# 1-Schematic_RFID_WAVER.net
KiCad netlist of a schematic drawn in EasyEDA
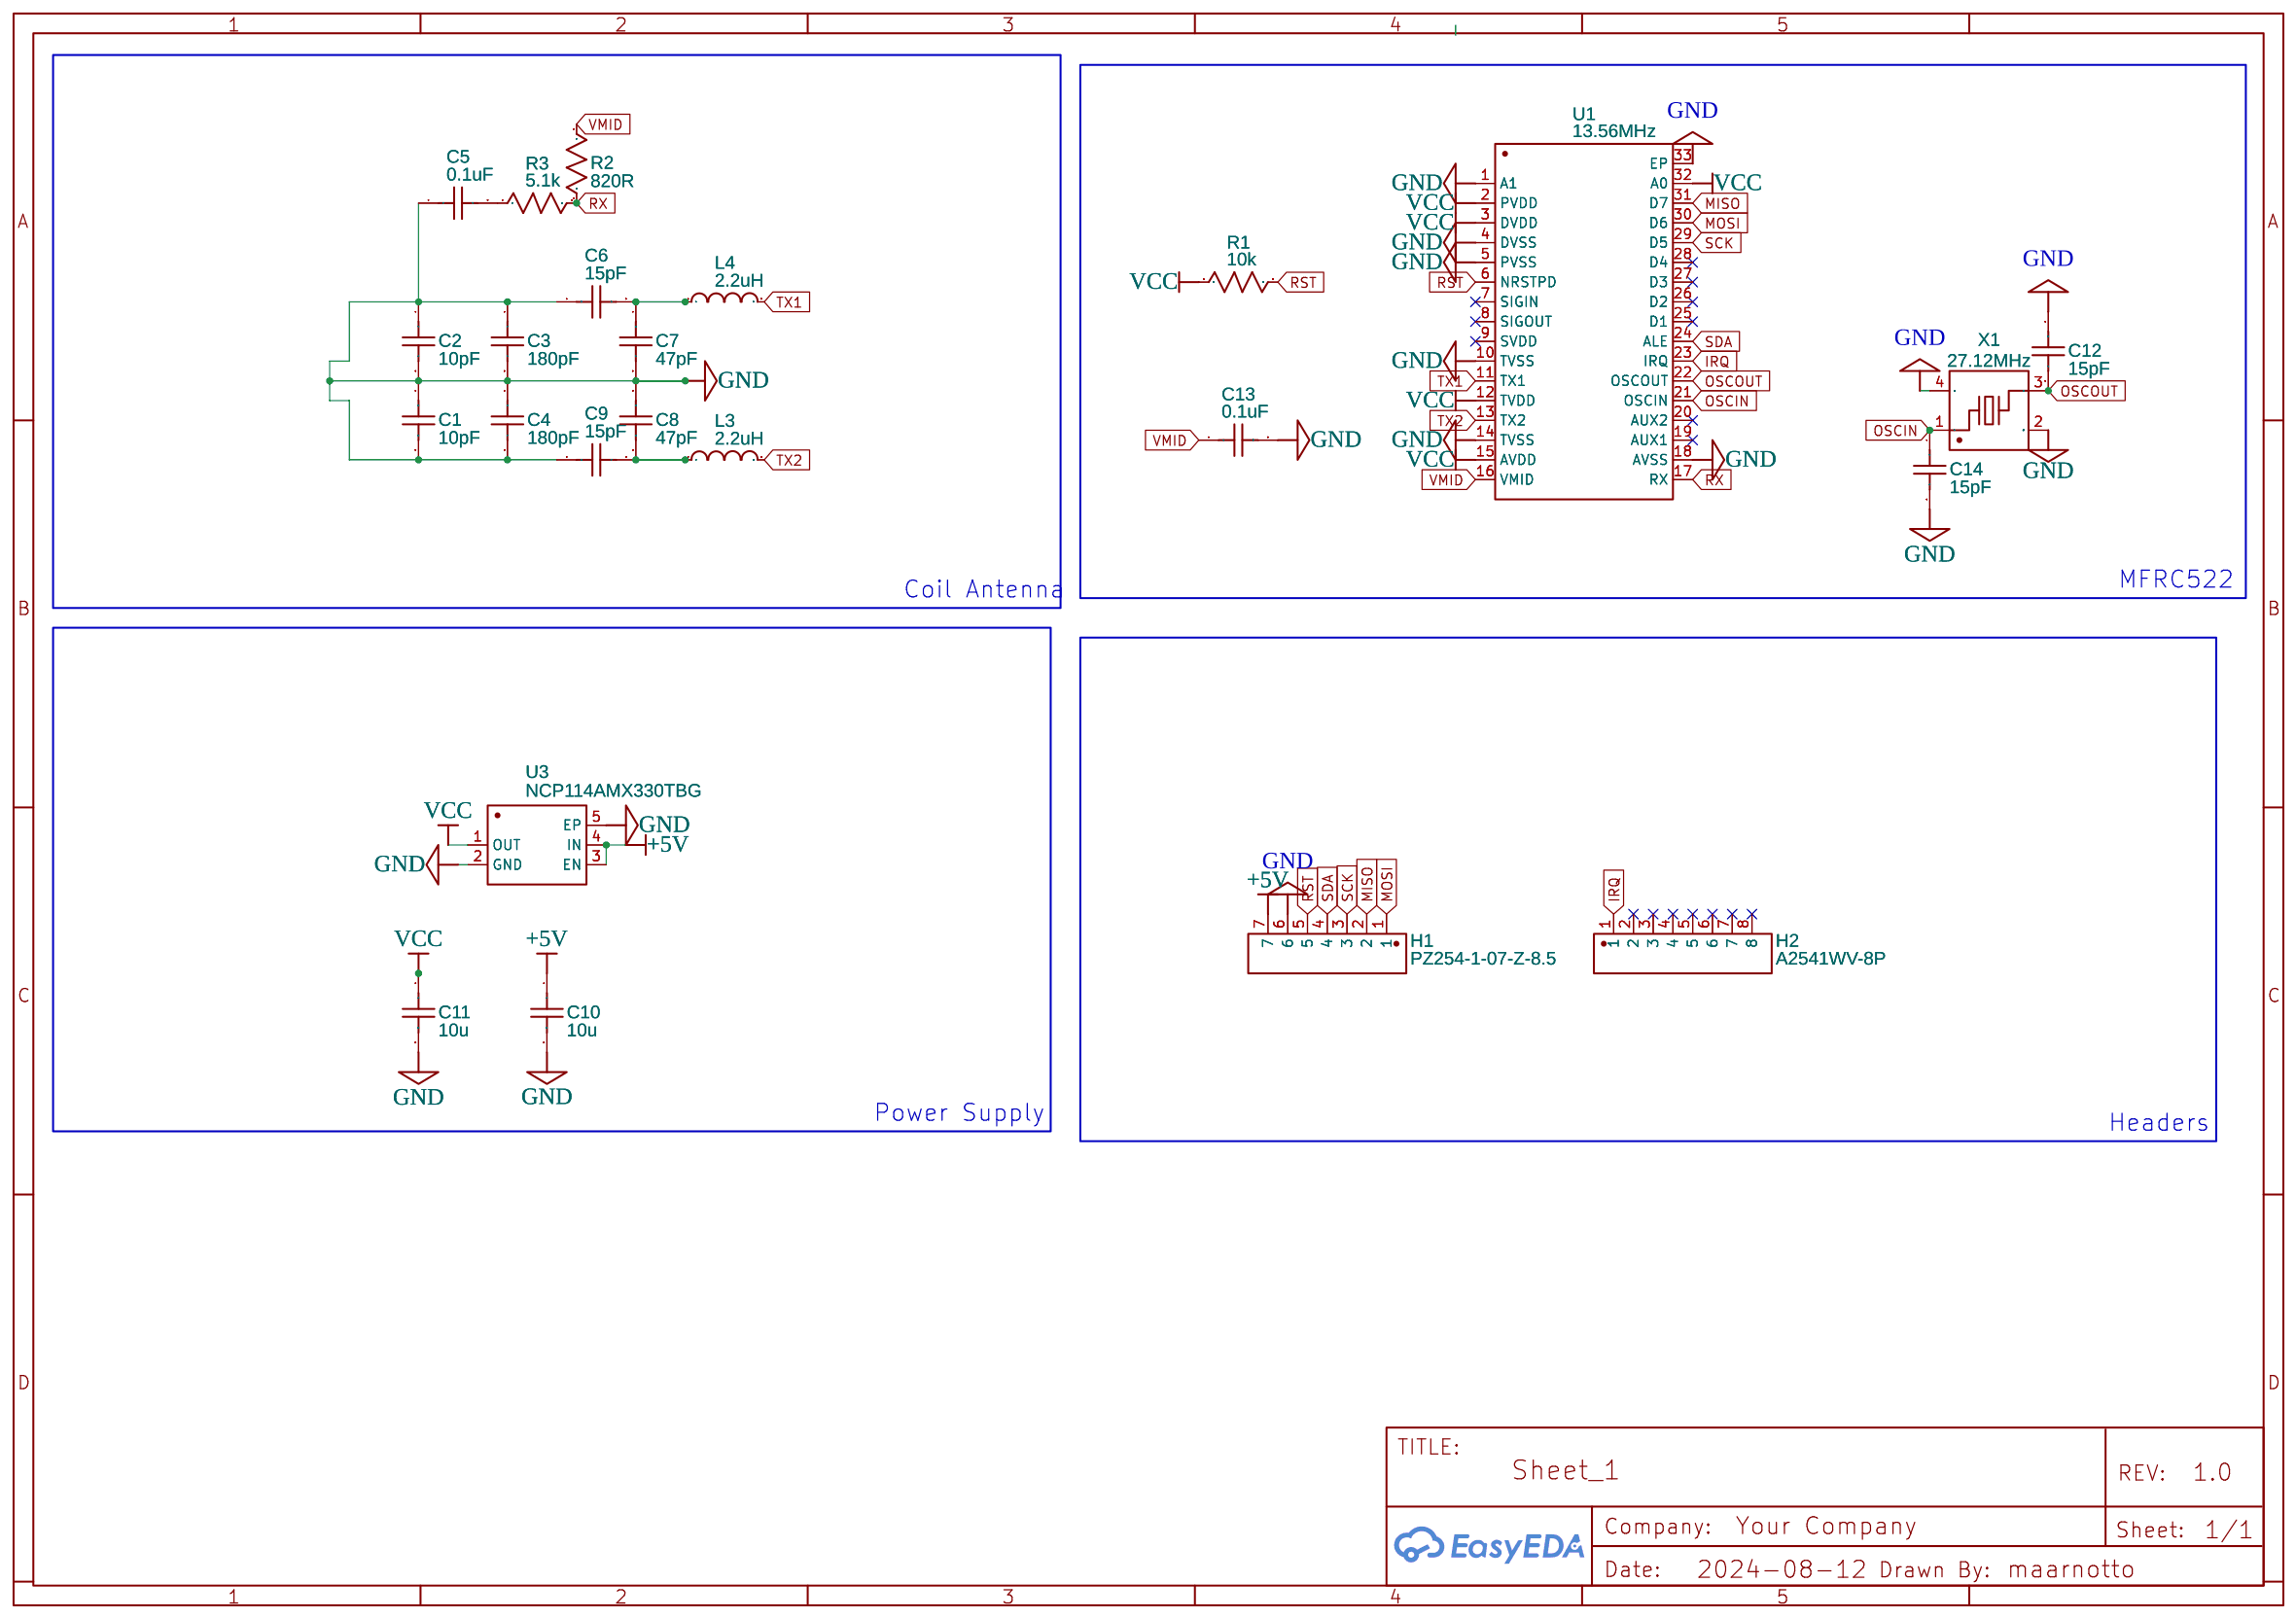
[diagram p0: schematic sheet]

(export (version "E")
  (design (tool "Eeschema 10.0.6"))
  (components
    (comp (ref "C1") (value "10pF") (libsource (lib "") (part "C_0603_US")))
    (comp (ref "C2") (value "10pF") (libsource (lib "") (part "C_0603_US")))
    (comp (ref "C3") (value "180pF") (libsource (lib "") (part "C_0603_US")))
    (comp (ref "C4") (value "180pF") (libsource (lib "") (part "C_0603_US")))
    (comp (ref "C5") (value "0.1uF") (libsource (lib "") (part "C_0603_US_1")))
    (comp (ref "C6") (value "15pF") (libsource (lib "") (part "C_0603_US_1")))
    (comp (ref "C7") (value "47pF") (libsource (lib "") (part "C_0603_US")))
    (comp (ref "C8") (value "47pF") (libsource (lib "") (part "C_0603_US")))
    (comp (ref "C9") (value "15pF") (libsource (lib "") (part "C_0603_US_1")))
    (comp (ref "C10") (value "10u") (libsource (lib "") (part "C_0603_US")))
    (comp (ref "C11") (value "10u") (libsource (lib "") (part "C_0603_US")))
    (comp (ref "C12") (value "15pF") (libsource (lib "") (part "C_0603_US")))
    (comp (ref "C13") (value "0.1uF") (libsource (lib "") (part "C_0603_US_1")))
    (comp (ref "C14") (value "15pF") (libsource (lib "") (part "C_0603_US")))
    (comp (ref "H1")
      (value "PZ254-1-07-Z-8.5")
      (fields (field (name "Manufacturer") "HCTL(华灿天禄)"))
      (libsource (lib "") (part "PZ254-1-07-Z-8.5"))
    )
    (comp (ref "H2")
      (value "A2541WV-8P")
      (fields (field (name "Manufacturer") "CJT(长江连接器)"))
      (libsource (lib "") (part "A2541WV-8P"))
    )
    (comp (ref "L3") (value "2.2uH") (libsource (lib "") (part "L0603_US")))
    (comp (ref "L4") (value "2.2uH") (libsource (lib "") (part "L0603_US")))
    (comp (ref "R1") (value "10k") (libsource (lib "") (part "R_0603_US")))
    (comp (ref "R2") (value "820R") (libsource (lib "") (part "R_0603_US_1")))
    (comp (ref "R3") (value "5.1k") (libsource (lib "") (part "R_0603_US")))
    (comp (ref "U1")
      (value "13.56MHz")
      (fields (field (name "Manufacturer Part") "MFRC522") (field (name "Manufacturer") "JSMSEMI(杰盛微)"))
      (libsource (lib "") (part "MFRC522"))
    )
    (comp (ref "U3")
      (value "NCP114AMX330TBG")
      (fields (field (name "Manufacturer") "onsemi(安森美)"))
      (libsource (lib "") (part "NCP114AMX330TBG"))
    )
    (comp (ref "X1")
      (value "27.12MHz")
      (fields
        (field (name "Manufacturer Part") "XL2EL89CMI-111YLC-27.12M")
        (field (name "Manufacturer") "YXC(扬兴晶振)")
      )
      (libsource (lib "") (part "XL2EL89CMI-111YLC-27.12M"))
    )
  )
  (nets
    (net (code "1") (name "+5V") (class "Default")
      (node (ref "C10") (pin "1") (pinfunction "1_1") (pintype "unspecified"))
      (node (ref "H1") (pin "7") (pinfunction "7_7") (pintype "unspecified"))
      (node (ref "U3") (pin "3") (pinfunction "EN_3") (pintype "unspecified"))
      (node (ref "U3") (pin "4") (pinfunction "IN_4") (pintype "unspecified"))
    )
    (net (code "2") (name "GND") (class "Default")
      (node (ref "C1") (pin "1") (pinfunction "1_1") (pintype "unspecified"))
      (node (ref "C1") (pin "2") (pinfunction "2_2") (pintype "unspecified"))
      (node (ref "C10") (pin "2") (pinfunction "2_2") (pintype "unspecified"))
      (node (ref "C11") (pin "2") (pinfunction "2_2") (pintype "unspecified"))
      (node (ref "C12") (pin "1") (pinfunction "1_1") (pintype "unspecified"))
      (node (ref "C13") (pin "2") (pinfunction "2_2") (pintype "unspecified"))
      (node (ref "C14") (pin "2") (pinfunction "2_2") (pintype "unspecified"))
      (node (ref "C2") (pin "1") (pinfunction "1_1") (pintype "unspecified"))
      (node (ref "C2") (pin "2") (pinfunction "2_2") (pintype "unspecified"))
      (node (ref "C3") (pin "1") (pinfunction "1_1") (pintype "unspecified"))
      (node (ref "C3") (pin "2") (pinfunction "2_2") (pintype "unspecified"))
      (node (ref "C4") (pin "1") (pinfunction "1_1") (pintype "unspecified"))
      (node (ref "C4") (pin "2") (pinfunction "2_2") (pintype "unspecified"))
      (node (ref "C5") (pin "1") (pinfunction "1_1") (pintype "unspecified"))
      (node (ref "C6") (pin "1") (pinfunction "1_1") (pintype "unspecified"))
      (node (ref "C7") (pin "2") (pinfunction "2_2") (pintype "unspecified"))
      (node (ref "C8") (pin "1") (pinfunction "1_1") (pintype "unspecified"))
      (node (ref "C9") (pin "1") (pinfunction "1_1") (pintype "unspecified"))
      (node (ref "H1") (pin "6") (pinfunction "6_6") (pintype "unspecified"))
      (node (ref "U1") (pin "1") (pinfunction "A1_1") (pintype "unspecified"))
      (node (ref "U1") (pin "10") (pinfunction "TVSS_10") (pintype "unspecified"))
      (node (ref "U1") (pin "14") (pinfunction "TVSS_14") (pintype "unspecified"))
      (node (ref "U1") (pin "18") (pinfunction "AVSS_18") (pintype "unspecified"))
      (node (ref "U1") (pin "33") (pinfunction "EP_33") (pintype "unspecified"))
      (node (ref "U1") (pin "4") (pinfunction "DVSS_4") (pintype "unspecified"))
      (node (ref "U1") (pin "5") (pinfunction "PVSS_5") (pintype "unspecified"))
      (node (ref "U3") (pin "2") (pinfunction "GND_2") (pintype "unspecified"))
      (node (ref "U3") (pin "5") (pinfunction "EP_5") (pintype "unspecified"))
      (node (ref "X1") (pin "2") (pinfunction "GND_2") (pintype "input"))
      (node (ref "X1") (pin "4") (pinfunction "GND_4") (pintype "input"))
    )
    (net (code "3") (name "IRQ") (class "Default")
      (node (ref "H2") (pin "1") (pinfunction "1_1") (pintype "unspecified"))
      (node (ref "U1") (pin "23") (pinfunction "IRQ_23") (pintype "unspecified"))
    )
    (net (code "4") (name "MISO") (class "Default")
      (node (ref "H1") (pin "2") (pinfunction "2_2") (pintype "unspecified"))
      (node (ref "U1") (pin "31") (pinfunction "D7_31") (pintype "unspecified"))
    )
    (net (code "5") (name "MOSI") (class "Default")
      (node (ref "H1") (pin "1") (pinfunction "1_1") (pintype "unspecified"))
      (node (ref "U1") (pin "30") (pinfunction "D6_30") (pintype "unspecified"))
    )
    (net (code "6") (name "Net-(C5-Pad2)") (class "Default")
      (node (ref "C5") (pin "2") (pinfunction "2_2") (pintype "unspecified"))
      (node (ref "R3") (pin "1") (pinfunction "1_1") (pintype "unspecified"))
    )
    (net (code "7") (name "Net-(C6-Pad2)") (class "Default")
      (node (ref "C6") (pin "2") (pinfunction "2_2") (pintype "unspecified"))
      (node (ref "C7") (pin "1") (pinfunction "1_1") (pintype "unspecified"))
      (node (ref "L4") (pin "1") (pinfunction "1_1") (pintype "unspecified"))
    )
    (net (code "8") (name "Net-(C8-Pad2)") (class "Default")
      (node (ref "C8") (pin "2") (pinfunction "2_2") (pintype "unspecified"))
      (node (ref "C9") (pin "2") (pinfunction "2_2") (pintype "unspecified"))
      (node (ref "L3") (pin "1") (pinfunction "1_1") (pintype "unspecified"))
    )
    (net (code "9") (name "OSCIN") (class "Default")
      (node (ref "C14") (pin "1") (pinfunction "1_1") (pintype "unspecified"))
      (node (ref "U1") (pin "21") (pinfunction "OSCIN_21") (pintype "unspecified"))
      (node (ref "X1") (pin "1") (pinfunction "1_1") (pintype "input"))
    )
    (net (code "10") (name "OSCOUT") (class "Default")
      (node (ref "C12") (pin "2") (pinfunction "2_2") (pintype "unspecified"))
      (node (ref "U1") (pin "22") (pinfunction "OSCOUT_22") (pintype "unspecified"))
      (node (ref "X1") (pin "3") (pinfunction "3_3") (pintype "input"))
    )
    (net (code "11") (name "RST") (class "Default")
      (node (ref "H1") (pin "5") (pinfunction "5_5") (pintype "unspecified"))
      (node (ref "R1") (pin "2") (pinfunction "2_2") (pintype "unspecified"))
      (node (ref "U1") (pin "6") (pinfunction "NRSTPD_6") (pintype "unspecified"))
    )
    (net (code "12") (name "RX") (class "Default")
      (node (ref "R2") (pin "2") (pinfunction "2_2") (pintype "unspecified"))
      (node (ref "R3") (pin "2") (pinfunction "2_2") (pintype "unspecified"))
      (node (ref "U1") (pin "17") (pinfunction "RX_17") (pintype "unspecified"))
    )
    (net (code "13") (name "SCK") (class "Default")
      (node (ref "H1") (pin "3") (pinfunction "3_3") (pintype "unspecified"))
      (node (ref "U1") (pin "29") (pinfunction "D5_29") (pintype "unspecified"))
    )
    (net (code "14") (name "SDA") (class "Default")
      (node (ref "H1") (pin "4") (pinfunction "4_4") (pintype "unspecified"))
      (node (ref "U1") (pin "24") (pinfunction "ALE_24") (pintype "unspecified"))
    )
    (net (code "15") (name "TX1") (class "Default")
      (node (ref "L4") (pin "2") (pinfunction "2_2") (pintype "unspecified"))
      (node (ref "U1") (pin "11") (pinfunction "TX1_11") (pintype "unspecified"))
    )
    (net (code "16") (name "TX2") (class "Default")
      (node (ref "L3") (pin "2") (pinfunction "2_2") (pintype "unspecified"))
      (node (ref "U1") (pin "13") (pinfunction "TX2_13") (pintype "unspecified"))
    )
    (net (code "17") (name "VCC") (class "Default")
      (node (ref "C11") (pin "1") (pinfunction "1_1") (pintype "unspecified"))
      (node (ref "R1") (pin "1") (pinfunction "1_1") (pintype "unspecified"))
      (node (ref "U1") (pin "12") (pinfunction "TVDD_12") (pintype "unspecified"))
      (node (ref "U1") (pin "15") (pinfunction "AVDD_15") (pintype "unspecified"))
      (node (ref "U1") (pin "2") (pinfunction "PVDD_2") (pintype "unspecified"))
      (node (ref "U1") (pin "3") (pinfunction "DVDD_3") (pintype "unspecified"))
      (node (ref "U1") (pin "32") (pinfunction "A0_32") (pintype "unspecified"))
      (node (ref "U3") (pin "1") (pinfunction "OUT_1") (pintype "unspecified"))
    )
    (net (code "18") (name "VMID") (class "Default")
      (node (ref "C13") (pin "1") (pinfunction "1_1") (pintype "unspecified"))
      (node (ref "R2") (pin "1") (pinfunction "1_1") (pintype "unspecified"))
      (node (ref "U1") (pin "16") (pinfunction "VMID_16") (pintype "unspecified"))
    )
    (net (code "19") (name "unconnected-(H2-Pad2)") (class "Default")
      (node (ref "H2") (pin "2") (pinfunction "2_2") (pintype "unspecified+no_connect"))
    )
    (net (code "20") (name "unconnected-(H2-Pad3)") (class "Default")
      (node (ref "H2") (pin "3") (pinfunction "3_3") (pintype "unspecified+no_connect"))
    )
    (net (code "21") (name "unconnected-(H2-Pad4)") (class "Default")
      (node (ref "H2") (pin "4") (pinfunction "4_4") (pintype "unspecified+no_connect"))
    )
    (net (code "22") (name "unconnected-(H2-Pad5)") (class "Default")
      (node (ref "H2") (pin "5") (pinfunction "5_5") (pintype "unspecified+no_connect"))
    )
    (net (code "23") (name "unconnected-(H2-Pad6)") (class "Default")
      (node (ref "H2") (pin "6") (pinfunction "6_6") (pintype "unspecified+no_connect"))
    )
    (net (code "24") (name "unconnected-(H2-Pad7)") (class "Default")
      (node (ref "H2") (pin "7") (pinfunction "7_7") (pintype "unspecified+no_connect"))
    )
    (net (code "25") (name "unconnected-(H2-Pad8)") (class "Default")
      (node (ref "H2") (pin "8") (pinfunction "8_8") (pintype "unspecified+no_connect"))
    )
    (net (code "26") (name "unconnected-(U1-AUX1-Pad19)") (class "Default")
      (node (ref "U1") (pin "19") (pinfunction "AUX1_19") (pintype "unspecified+no_connect"))
    )
    (net (code "27") (name "unconnected-(U1-AUX2-Pad20)") (class "Default")
      (node (ref "U1") (pin "20") (pinfunction "AUX2_20") (pintype "unspecified+no_connect"))
    )
    (net (code "28") (name "unconnected-(U1-D1-Pad25)") (class "Default")
      (node (ref "U1") (pin "25") (pinfunction "D1_25") (pintype "unspecified+no_connect"))
    )
    (net (code "29") (name "unconnected-(U1-D2-Pad26)") (class "Default")
      (node (ref "U1") (pin "26") (pinfunction "D2_26") (pintype "unspecified+no_connect"))
    )
    (net (code "30") (name "unconnected-(U1-D3-Pad27)") (class "Default")
      (node (ref "U1") (pin "27") (pinfunction "D3_27") (pintype "unspecified+no_connect"))
    )
    (net (code "31") (name "unconnected-(U1-D4-Pad28)") (class "Default")
      (node (ref "U1") (pin "28") (pinfunction "D4_28") (pintype "unspecified+no_connect"))
    )
    (net (code "32") (name "unconnected-(U1-SIGIN-Pad7)") (class "Default")
      (node (ref "U1") (pin "7") (pinfunction "SIGIN_7") (pintype "unspecified+no_connect"))
    )
    (net (code "33") (name "unconnected-(U1-SIGOUT-Pad8)") (class "Default")
      (node (ref "U1") (pin "8") (pinfunction "SIGOUT_8") (pintype "unspecified+no_connect"))
    )
    (net (code "34") (name "unconnected-(U1-SVDD-Pad9)") (class "Default")
      (node (ref "U1") (pin "9") (pinfunction "SVDD_9") (pintype "unspecified+no_connect"))
    )
  )
)
